# SH4_-_LEVEL_SHIFTERS.net
KiCad netlist of a schematic drawn in Altium Designer
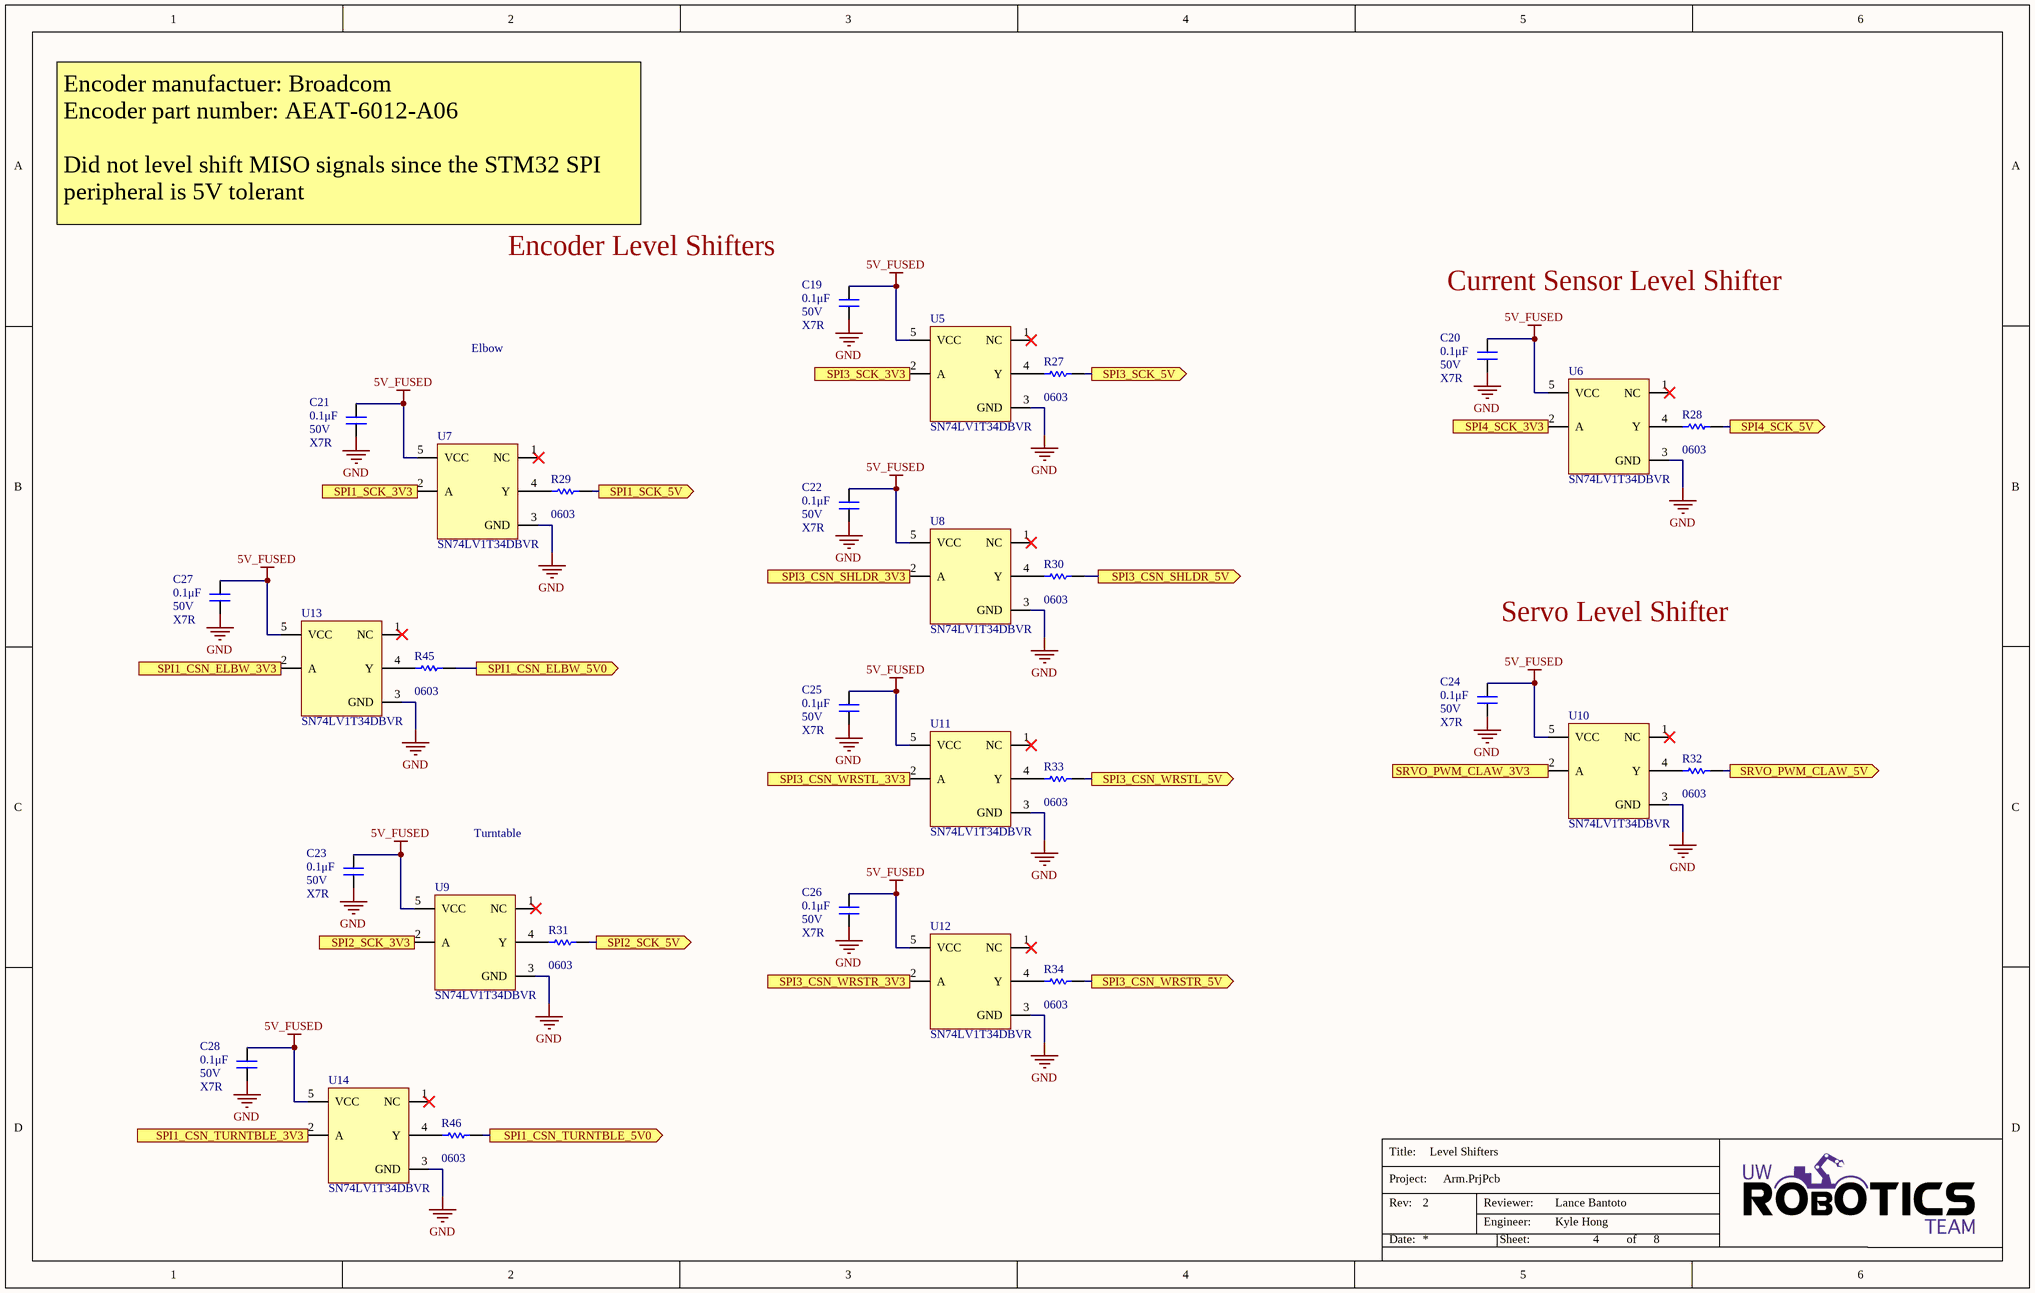
[diagram p0: SH4 - LEVEL SHIFTERS.SchDoc]

(export (version "E")
  (design (tool "Eeschema 10.0.6"))
  (components
    (comp (ref "C19")
      (value "0.1μF")
      (footprint "CAP0603")
      (description "CAP CER 0.1UF 50V X7R 0603")
      (fields
        (field (name "DIELECTRIC") "X7R")
        (field (name "VOLTAGE RATING") "50V")
        (field (name "Comment") "CAP_0.1uF_50V_0603")
      )
      (libsource (lib "UWRT_Schematic_Library_2020") (part "CAP_0.1uF_50V_0603"))
    )
    (comp (ref "C20")
      (value "0.1μF")
      (footprint "CAP0603")
      (description "CAP CER 0.1UF 50V X7R 0603")
      (fields
        (field (name "DIELECTRIC") "X7R")
        (field (name "VOLTAGE RATING") "50V")
        (field (name "Comment") "CAP_0.1uF_50V_0603")
      )
      (libsource (lib "UWRT_Schematic_Library_2020") (part "CAP_0.1uF_50V_0603"))
    )
    (comp (ref "C21")
      (value "0.1μF")
      (footprint "CAP0603")
      (description "CAP CER 0.1UF 50V X7R 0603")
      (fields
        (field (name "DIELECTRIC") "X7R")
        (field (name "VOLTAGE RATING") "50V")
        (field (name "Comment") "CAP_0.1uF_50V_0603")
      )
      (libsource (lib "UWRT_Schematic_Library_2020") (part "CAP_0.1uF_50V_0603"))
    )
    (comp (ref "C22")
      (value "0.1μF")
      (footprint "CAP0603")
      (description "CAP CER 0.1UF 50V X7R 0603")
      (fields
        (field (name "DIELECTRIC") "X7R")
        (field (name "VOLTAGE RATING") "50V")
        (field (name "Comment") "CAP_0.1uF_50V_0603")
      )
      (libsource (lib "UWRT_Schematic_Library_2020") (part "CAP_0.1uF_50V_0603"))
    )
    (comp (ref "C23")
      (value "0.1μF")
      (footprint "CAP0603")
      (description "CAP CER 0.1UF 50V X7R 0603")
      (fields
        (field (name "DIELECTRIC") "X7R")
        (field (name "VOLTAGE RATING") "50V")
        (field (name "Comment") "CAP_0.1uF_50V_0603")
      )
      (libsource (lib "UWRT_Schematic_Library_2020") (part "CAP_0.1uF_50V_0603"))
    )
    (comp (ref "C24")
      (value "0.1μF")
      (footprint "CAP0603")
      (description "CAP CER 0.1UF 50V X7R 0603")
      (fields
        (field (name "DIELECTRIC") "X7R")
        (field (name "VOLTAGE RATING") "50V")
        (field (name "Comment") "CAP_0.1uF_50V_0603")
      )
      (libsource (lib "UWRT_Schematic_Library_2020") (part "CAP_0.1uF_50V_0603"))
    )
    (comp (ref "C25")
      (value "0.1μF")
      (footprint "CAP0603")
      (description "CAP CER 0.1UF 50V X7R 0603")
      (fields
        (field (name "DIELECTRIC") "X7R")
        (field (name "VOLTAGE RATING") "50V")
        (field (name "Comment") "CAP_0.1uF_50V_0603")
      )
      (libsource (lib "UWRT_Schematic_Library_2020") (part "CAP_0.1uF_50V_0603"))
    )
    (comp (ref "C26")
      (value "0.1μF")
      (footprint "CAP0603")
      (description "CAP CER 0.1UF 50V X7R 0603")
      (fields
        (field (name "DIELECTRIC") "X7R")
        (field (name "VOLTAGE RATING") "50V")
        (field (name "Comment") "CAP_0.1uF_50V_0603")
      )
      (libsource (lib "UWRT_Schematic_Library_2020") (part "CAP_0.1uF_50V_0603"))
    )
    (comp (ref "C27")
      (value "0.1μF")
      (footprint "CAP0603")
      (description "CAP CER 0.1UF 50V X7R 0603")
      (fields
        (field (name "DIELECTRIC") "X7R")
        (field (name "VOLTAGE RATING") "50V")
        (field (name "Comment") "CAP_0.1uF_50V_0603")
      )
      (libsource (lib "UWRT_Schematic_Library_2020") (part "CAP_0.1uF_50V_0603"))
    )
    (comp (ref "C28")
      (value "0.1μF")
      (footprint "CAP0603")
      (description "CAP CER 0.1UF 50V X7R 0603")
      (fields
        (field (name "DIELECTRIC") "X7R")
        (field (name "VOLTAGE RATING") "50V")
        (field (name "Comment") "CAP_0.1uF_50V_0603")
      )
      (libsource (lib "UWRT_Schematic_Library_2020") (part "CAP_0.1uF_50V_0603"))
    )
    (comp (ref "R27")
      (value "RES_33Ω_0603_1%")
      (footprint "RESC0603")
      (description "RES 33 OHM 1% 1/10W 0603")
      (fields (field (name "PACKAGE/FOOTPRINT") "0603"))
      (libsource (lib "UWRT_Schematic_Library_2020") (part "RES_33Ω_0603_1%"))
    )
    (comp (ref "R28")
      (value "RES_33Ω_0603_1%")
      (footprint "RESC0603")
      (description "RES 33 OHM 1% 1/10W 0603")
      (fields (field (name "PACKAGE/FOOTPRINT") "0603"))
      (libsource (lib "UWRT_Schematic_Library_2020") (part "RES_33Ω_0603_1%"))
    )
    (comp (ref "R29")
      (value "RES_33Ω_0603_1%")
      (footprint "RESC0603")
      (description "RES 33 OHM 1% 1/10W 0603")
      (fields (field (name "PACKAGE/FOOTPRINT") "0603"))
      (libsource (lib "UWRT_Schematic_Library_2020") (part "RES_33Ω_0603_1%"))
    )
    (comp (ref "R30")
      (value "RES_33Ω_0603_1%")
      (footprint "RESC0603")
      (description "RES 33 OHM 1% 1/10W 0603")
      (fields (field (name "PACKAGE/FOOTPRINT") "0603"))
      (libsource (lib "UWRT_Schematic_Library_2020") (part "RES_33Ω_0603_1%"))
    )
    (comp (ref "R31")
      (value "RES_33Ω_0603_1%")
      (footprint "RESC0603")
      (description "RES 33 OHM 1% 1/10W 0603")
      (fields (field (name "PACKAGE/FOOTPRINT") "0603"))
      (libsource (lib "UWRT_Schematic_Library_2020") (part "RES_33Ω_0603_1%"))
    )
    (comp (ref "R32")
      (value "RES_33Ω_0603_1%")
      (footprint "RESC0603")
      (description "RES 33 OHM 1% 1/10W 0603")
      (fields (field (name "PACKAGE/FOOTPRINT") "0603"))
      (libsource (lib "UWRT_Schematic_Library_2020") (part "RES_33Ω_0603_1%"))
    )
    (comp (ref "R33")
      (value "RES_33Ω_0603_1%")
      (footprint "RESC0603")
      (description "RES 33 OHM 1% 1/10W 0603")
      (fields (field (name "PACKAGE/FOOTPRINT") "0603"))
      (libsource (lib "UWRT_Schematic_Library_2020") (part "RES_33Ω_0603_1%"))
    )
    (comp (ref "R34")
      (value "RES_33Ω_0603_1%")
      (footprint "RESC0603")
      (description "RES 33 OHM 1% 1/10W 0603")
      (fields (field (name "PACKAGE/FOOTPRINT") "0603"))
      (libsource (lib "UWRT_Schematic_Library_2020") (part "RES_33Ω_0603_1%"))
    )
    (comp (ref "R45")
      (value "RES_33Ω_0603_1%")
      (footprint "RESC0603")
      (description "RES 33 OHM 1% 1/10W 0603")
      (fields (field (name "PACKAGE/FOOTPRINT") "0603"))
      (libsource (lib "UWRT_Schematic_Library_2020") (part "RES_33Ω_0603_1%"))
    )
    (comp (ref "R46")
      (value "RES_33Ω_0603_1%")
      (footprint "RESC0603")
      (description "RES 33 OHM 1% 1/10W 0603")
      (fields (field (name "PACKAGE/FOOTPRINT") "0603"))
      (libsource (lib "UWRT_Schematic_Library_2020") (part "RES_33Ω_0603_1%"))
    )
    (comp (ref "U5")
      (value "SN74LV1T34")
      (footprint "SN74LV1T34DBVR")
      (description "IC BUF NON-INVERT 5.5V SOT23-5")
      (fields
        (field (name "MANUFACTURER PART NUMBER 1") "SN74LV1T34DBVR")
        (field (name "LCSC PART #") "C100024")
      )
      (libsource (lib "UWRT_Schematic_Library_2020") (part "SN74LV1T34"))
    )
    (comp (ref "U6")
      (value "SN74LV1T34")
      (footprint "SN74LV1T34DBVR")
      (description "IC BUF NON-INVERT 5.5V SOT23-5")
      (fields
        (field (name "MANUFACTURER PART NUMBER 1") "SN74LV1T34DBVR")
        (field (name "LCSC PART #") "C100024")
      )
      (libsource (lib "UWRT_Schematic_Library_2020") (part "SN74LV1T34"))
    )
    (comp (ref "U7")
      (value "SN74LV1T34")
      (footprint "SN74LV1T34DBVR")
      (description "IC BUF NON-INVERT 5.5V SOT23-5")
      (fields
        (field (name "MANUFACTURER PART NUMBER 1") "SN74LV1T34DBVR")
        (field (name "LCSC PART #") "C100024")
      )
      (libsource (lib "UWRT_Schematic_Library_2020") (part "SN74LV1T34"))
    )
    (comp (ref "U8")
      (value "SN74LV1T34")
      (footprint "SN74LV1T34DBVR")
      (description "IC BUF NON-INVERT 5.5V SOT23-5")
      (fields
        (field (name "MANUFACTURER PART NUMBER 1") "SN74LV1T34DBVR")
        (field (name "LCSC PART #") "C100024")
      )
      (libsource (lib "UWRT_Schematic_Library_2020") (part "SN74LV1T34"))
    )
    (comp (ref "U9")
      (value "SN74LV1T34")
      (footprint "SN74LV1T34DBVR")
      (description "IC BUF NON-INVERT 5.5V SOT23-5")
      (fields
        (field (name "MANUFACTURER PART NUMBER 1") "SN74LV1T34DBVR")
        (field (name "LCSC PART #") "C100024")
      )
      (libsource (lib "UWRT_Schematic_Library_2020") (part "SN74LV1T34"))
    )
    (comp (ref "U10")
      (value "SN74LV1T34")
      (footprint "SN74LV1T34DBVR")
      (description "IC BUF NON-INVERT 5.5V SOT23-5")
      (fields
        (field (name "MANUFACTURER PART NUMBER 1") "SN74LV1T34DBVR")
        (field (name "LCSC PART #") "C100024")
      )
      (libsource (lib "UWRT_Schematic_Library_2020") (part "SN74LV1T34"))
    )
    (comp (ref "U11")
      (value "SN74LV1T34")
      (footprint "SN74LV1T34DBVR")
      (description "IC BUF NON-INVERT 5.5V SOT23-5")
      (fields
        (field (name "MANUFACTURER PART NUMBER 1") "SN74LV1T34DBVR")
        (field (name "LCSC PART #") "C100024")
      )
      (libsource (lib "UWRT_Schematic_Library_2020") (part "SN74LV1T34"))
    )
    (comp (ref "U12")
      (value "SN74LV1T34")
      (footprint "SN74LV1T34DBVR")
      (description "IC BUF NON-INVERT 5.5V SOT23-5")
      (fields
        (field (name "MANUFACTURER PART NUMBER 1") "SN74LV1T34DBVR")
        (field (name "LCSC PART #") "C100024")
      )
      (libsource (lib "UWRT_Schematic_Library_2020") (part "SN74LV1T34"))
    )
    (comp (ref "U13")
      (value "SN74LV1T34")
      (footprint "SN74LV1T34DBVR")
      (description "IC BUF NON-INVERT 5.5V SOT23-5")
      (fields
        (field (name "MANUFACTURER PART NUMBER 1") "SN74LV1T34DBVR")
        (field (name "LCSC PART #") "C100024")
      )
      (libsource (lib "UWRT_Schematic_Library_2020") (part "SN74LV1T34"))
    )
    (comp (ref "U14")
      (value "SN74LV1T34")
      (footprint "SN74LV1T34DBVR")
      (description "IC BUF NON-INVERT 5.5V SOT23-5")
      (fields
        (field (name "MANUFACTURER PART NUMBER 1") "SN74LV1T34DBVR")
        (field (name "LCSC PART #") "C100024")
      )
      (libsource (lib "UWRT_Schematic_Library_2020") (part "SN74LV1T34"))
    )
  )
  (nets
    (net (code "1") (name "/SPI1_CSN_ELBW_3V3") (class "Default")
      (node (ref "U13") (pin "2") (pinfunction "A_2") (pintype "passive"))
    )
    (net (code "2") (name "/SPI1_CSN_ELBW_5V0") (class "Default")
      (node (ref "R45") (pin "2") (pinfunction "2_2") (pintype "passive"))
    )
    (net (code "3") (name "/SPI1_CSN_TURNTBLE_3V3") (class "Default")
      (node (ref "U14") (pin "2") (pinfunction "A_2") (pintype "passive"))
    )
    (net (code "4") (name "/SPI1_CSN_TURNTBLE_5V0") (class "Default")
      (node (ref "R46") (pin "2") (pinfunction "2_2") (pintype "passive"))
    )
    (net (code "5") (name "/SPI1_SCK_3V3") (class "Default")
      (node (ref "U7") (pin "2") (pinfunction "A_2") (pintype "passive"))
    )
    (net (code "6") (name "/SPI1_SCK_5V") (class "Default")
      (node (ref "R29") (pin "2") (pinfunction "2_2") (pintype "passive"))
    )
    (net (code "7") (name "/SPI2_SCK_3V3") (class "Default")
      (node (ref "U9") (pin "2") (pinfunction "A_2") (pintype "passive"))
    )
    (net (code "8") (name "/SPI2_SCK_5V") (class "Default")
      (node (ref "R31") (pin "2") (pinfunction "2_2") (pintype "passive"))
    )
    (net (code "9") (name "/SPI3_CSN_SHLDR_3V3") (class "Default")
      (node (ref "U8") (pin "2") (pinfunction "A_2") (pintype "passive"))
    )
    (net (code "10") (name "/SPI3_CSN_SHLDR_5V") (class "Default")
      (node (ref "R30") (pin "2") (pinfunction "2_2") (pintype "passive"))
    )
    (net (code "11") (name "/SPI3_CSN_WRSTL_3V3") (class "Default")
      (node (ref "U11") (pin "2") (pinfunction "A_2") (pintype "passive"))
    )
    (net (code "12") (name "/SPI3_CSN_WRSTL_5V") (class "Default")
      (node (ref "R33") (pin "2") (pinfunction "2_2") (pintype "passive"))
    )
    (net (code "13") (name "/SPI3_CSN_WRSTR_3V3") (class "Default")
      (node (ref "U12") (pin "2") (pinfunction "A_2") (pintype "passive"))
    )
    (net (code "14") (name "/SPI3_CSN_WRSTR_5V") (class "Default")
      (node (ref "R34") (pin "2") (pinfunction "2_2") (pintype "passive"))
    )
    (net (code "15") (name "/SPI3_SCK_3V3") (class "Default")
      (node (ref "U5") (pin "2") (pinfunction "A_2") (pintype "passive"))
    )
    (net (code "16") (name "/SPI3_SCK_5V") (class "Default")
      (node (ref "R27") (pin "2") (pinfunction "2_2") (pintype "passive"))
    )
    (net (code "17") (name "/SPI4_SCK_3V3") (class "Default")
      (node (ref "U6") (pin "2") (pinfunction "A_2") (pintype "passive"))
    )
    (net (code "18") (name "/SPI4_SCK_5V") (class "Default")
      (node (ref "R28") (pin "2") (pinfunction "2_2") (pintype "passive"))
    )
    (net (code "19") (name "/SRVO_PWM_CLAW_3V3") (class "Default")
      (node (ref "U10") (pin "2") (pinfunction "A_2") (pintype "passive"))
    )
    (net (code "20") (name "/SRVO_PWM_CLAW_5V") (class "Default")
      (node (ref "R32") (pin "2") (pinfunction "2_2") (pintype "passive"))
    )
    (net (code "21") (name "5V_FUSED") (class "Default")
      (node (ref "C19") (pin "2") (pinfunction "2_2") (pintype "passive"))
      (node (ref "C20") (pin "2") (pinfunction "2_2") (pintype "passive"))
      (node (ref "C21") (pin "2") (pinfunction "2_2") (pintype "passive"))
      (node (ref "C22") (pin "2") (pinfunction "2_2") (pintype "passive"))
      (node (ref "C23") (pin "2") (pinfunction "2_2") (pintype "passive"))
      (node (ref "C24") (pin "2") (pinfunction "2_2") (pintype "passive"))
      (node (ref "C25") (pin "2") (pinfunction "2_2") (pintype "passive"))
      (node (ref "C26") (pin "2") (pinfunction "2_2") (pintype "passive"))
      (node (ref "C27") (pin "2") (pinfunction "2_2") (pintype "passive"))
      (node (ref "C28") (pin "2") (pinfunction "2_2") (pintype "passive"))
      (node (ref "U10") (pin "5") (pinfunction "VCC_5") (pintype "passive"))
      (node (ref "U11") (pin "5") (pinfunction "VCC_5") (pintype "passive"))
      (node (ref "U12") (pin "5") (pinfunction "VCC_5") (pintype "passive"))
      (node (ref "U13") (pin "5") (pinfunction "VCC_5") (pintype "passive"))
      (node (ref "U14") (pin "5") (pinfunction "VCC_5") (pintype "passive"))
      (node (ref "U5") (pin "5") (pinfunction "VCC_5") (pintype "passive"))
      (node (ref "U6") (pin "5") (pinfunction "VCC_5") (pintype "passive"))
      (node (ref "U7") (pin "5") (pinfunction "VCC_5") (pintype "passive"))
      (node (ref "U8") (pin "5") (pinfunction "VCC_5") (pintype "passive"))
      (node (ref "U9") (pin "5") (pinfunction "VCC_5") (pintype "passive"))
    )
    (net (code "22") (name "GND") (class "Default")
      (node (ref "C19") (pin "1") (pinfunction "1_1") (pintype "passive"))
      (node (ref "C20") (pin "1") (pinfunction "1_1") (pintype "passive"))
      (node (ref "C21") (pin "1") (pinfunction "1_1") (pintype "passive"))
      (node (ref "C22") (pin "1") (pinfunction "1_1") (pintype "passive"))
      (node (ref "C23") (pin "1") (pinfunction "1_1") (pintype "passive"))
      (node (ref "C24") (pin "1") (pinfunction "1_1") (pintype "passive"))
      (node (ref "C25") (pin "1") (pinfunction "1_1") (pintype "passive"))
      (node (ref "C26") (pin "1") (pinfunction "1_1") (pintype "passive"))
      (node (ref "C27") (pin "1") (pinfunction "1_1") (pintype "passive"))
      (node (ref "C28") (pin "1") (pinfunction "1_1") (pintype "passive"))
      (node (ref "U10") (pin "3") (pinfunction "GND_3") (pintype "passive"))
      (node (ref "U11") (pin "3") (pinfunction "GND_3") (pintype "passive"))
      (node (ref "U12") (pin "3") (pinfunction "GND_3") (pintype "passive"))
      (node (ref "U13") (pin "3") (pinfunction "GND_3") (pintype "passive"))
      (node (ref "U14") (pin "3") (pinfunction "GND_3") (pintype "passive"))
      (node (ref "U5") (pin "3") (pinfunction "GND_3") (pintype "passive"))
      (node (ref "U6") (pin "3") (pinfunction "GND_3") (pintype "passive"))
      (node (ref "U7") (pin "3") (pinfunction "GND_3") (pintype "passive"))
      (node (ref "U8") (pin "3") (pinfunction "GND_3") (pintype "passive"))
      (node (ref "U9") (pin "3") (pinfunction "GND_3") (pintype "passive"))
    )
    (net (code "23") (name "Net-(U5-Y)") (class "Default")
      (node (ref "R27") (pin "1") (pinfunction "1_1") (pintype "passive"))
      (node (ref "U5") (pin "4") (pinfunction "Y_4") (pintype "passive"))
    )
    (net (code "24") (name "Net-(U6-Y)") (class "Default")
      (node (ref "R28") (pin "1") (pinfunction "1_1") (pintype "passive"))
      (node (ref "U6") (pin "4") (pinfunction "Y_4") (pintype "passive"))
    )
    (net (code "25") (name "Net-(U7-Y)") (class "Default")
      (node (ref "R29") (pin "1") (pinfunction "1_1") (pintype "passive"))
      (node (ref "U7") (pin "4") (pinfunction "Y_4") (pintype "passive"))
    )
    (net (code "26") (name "Net-(U8-Y)") (class "Default")
      (node (ref "R30") (pin "1") (pinfunction "1_1") (pintype "passive"))
      (node (ref "U8") (pin "4") (pinfunction "Y_4") (pintype "passive"))
    )
    (net (code "27") (name "Net-(U9-Y)") (class "Default")
      (node (ref "R31") (pin "1") (pinfunction "1_1") (pintype "passive"))
      (node (ref "U9") (pin "4") (pinfunction "Y_4") (pintype "passive"))
    )
    (net (code "28") (name "Net-(U10-Y)") (class "Default")
      (node (ref "R32") (pin "1") (pinfunction "1_1") (pintype "passive"))
      (node (ref "U10") (pin "4") (pinfunction "Y_4") (pintype "passive"))
    )
    (net (code "29") (name "Net-(U11-Y)") (class "Default")
      (node (ref "R33") (pin "1") (pinfunction "1_1") (pintype "passive"))
      (node (ref "U11") (pin "4") (pinfunction "Y_4") (pintype "passive"))
    )
    (net (code "30") (name "Net-(U12-Y)") (class "Default")
      (node (ref "R34") (pin "1") (pinfunction "1_1") (pintype "passive"))
      (node (ref "U12") (pin "4") (pinfunction "Y_4") (pintype "passive"))
    )
    (net (code "31") (name "Net-(U13-Y)") (class "Default")
      (node (ref "R45") (pin "1") (pinfunction "1_1") (pintype "passive"))
      (node (ref "U13") (pin "4") (pinfunction "Y_4") (pintype "passive"))
    )
    (net (code "32") (name "Net-(U14-Y)") (class "Default")
      (node (ref "R46") (pin "1") (pinfunction "1_1") (pintype "passive"))
      (node (ref "U14") (pin "4") (pinfunction "Y_4") (pintype "passive"))
    )
    (net (code "33") (name "unconnected-(U5-NC-Pad1)") (class "Default")
      (node (ref "U5") (pin "1") (pinfunction "NC_1") (pintype "passive+no_connect"))
    )
    (net (code "34") (name "unconnected-(U6-NC-Pad1)") (class "Default")
      (node (ref "U6") (pin "1") (pinfunction "NC_1") (pintype "passive+no_connect"))
    )
    (net (code "35") (name "unconnected-(U7-NC-Pad1)") (class "Default")
      (node (ref "U7") (pin "1") (pinfunction "NC_1") (pintype "passive+no_connect"))
    )
    (net (code "36") (name "unconnected-(U8-NC-Pad1)") (class "Default")
      (node (ref "U8") (pin "1") (pinfunction "NC_1") (pintype "passive+no_connect"))
    )
    (net (code "37") (name "unconnected-(U9-NC-Pad1)") (class "Default")
      (node (ref "U9") (pin "1") (pinfunction "NC_1") (pintype "passive+no_connect"))
    )
    (net (code "38") (name "unconnected-(U10-NC-Pad1)") (class "Default")
      (node (ref "U10") (pin "1") (pinfunction "NC_1") (pintype "passive+no_connect"))
    )
    (net (code "39") (name "unconnected-(U11-NC-Pad1)") (class "Default")
      (node (ref "U11") (pin "1") (pinfunction "NC_1") (pintype "passive+no_connect"))
    )
    (net (code "40") (name "unconnected-(U12-NC-Pad1)") (class "Default")
      (node (ref "U12") (pin "1") (pinfunction "NC_1") (pintype "passive+no_connect"))
    )
    (net (code "41") (name "unconnected-(U13-NC-Pad1)") (class "Default")
      (node (ref "U13") (pin "1") (pinfunction "NC_1") (pintype "passive+no_connect"))
    )
    (net (code "42") (name "unconnected-(U14-NC-Pad1)") (class "Default")
      (node (ref "U14") (pin "1") (pinfunction "NC_1") (pintype "passive+no_connect"))
    )
  )
)
